# binarybox-barrel.net
KiCad netlist of a schematic drawn in EAGLE
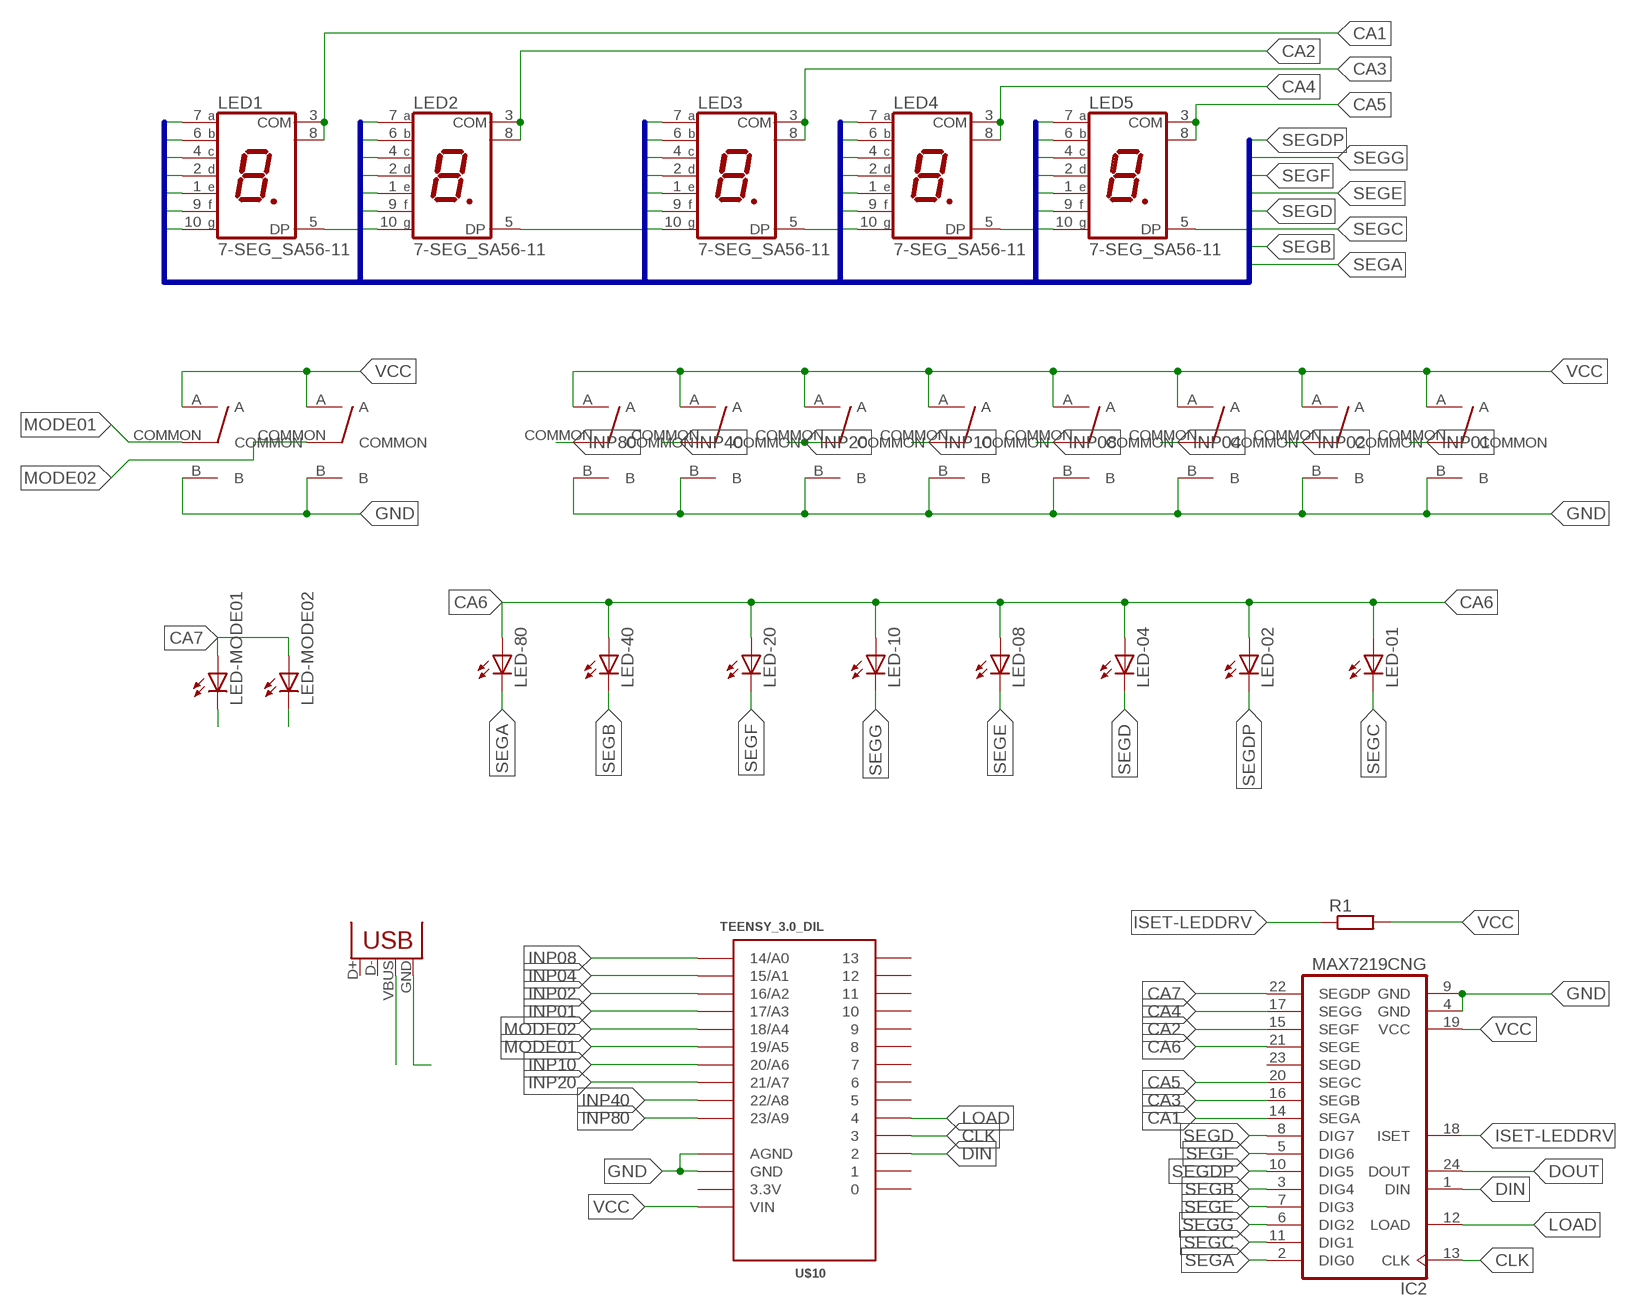
[diagram p0: schematic, sheet 1]

(export (version "E")
  (design (tool "Eeschema 10.0.6"))
  (components
    (comp (ref "IC2")
      (value "MAX7219CNG")
      (footprint "eagle-import:DIL24-3")
      (fields (field (name "MF") "MAXIM"))
      (libsource (lib "eagle-import") (part "MAX7219CNG"))
    )
    (comp (ref "LED-01")
      (value "LED5MM")
      (footprint "eagle-import:LED5MM")
      (libsource (lib "eagle-import") (part "LED5MM"))
    )
    (comp (ref "LED-02")
      (value "LED5MM")
      (footprint "eagle-import:LED5MM")
      (libsource (lib "eagle-import") (part "LED5MM"))
    )
    (comp (ref "LED-04")
      (value "LED5MM")
      (footprint "eagle-import:LED5MM")
      (libsource (lib "eagle-import") (part "LED5MM"))
    )
    (comp (ref "LED-08")
      (value "LED5MM")
      (footprint "eagle-import:LED5MM")
      (libsource (lib "eagle-import") (part "LED5MM"))
    )
    (comp (ref "LED-10")
      (value "LED5MM")
      (footprint "eagle-import:LED5MM")
      (libsource (lib "eagle-import") (part "LED5MM"))
    )
    (comp (ref "LED-20")
      (value "LED5MM")
      (footprint "eagle-import:LED5MM")
      (libsource (lib "eagle-import") (part "LED5MM"))
    )
    (comp (ref "LED-40")
      (value "LED5MM")
      (footprint "eagle-import:LED5MM")
      (libsource (lib "eagle-import") (part "LED5MM"))
    )
    (comp (ref "LED-80")
      (value "LED5MM")
      (footprint "eagle-import:LED5MM")
      (libsource (lib "eagle-import") (part "LED5MM"))
    )
    (comp (ref "LED-MODE01")
      (value "LED5MM")
      (footprint "eagle-import:LED5MM")
      (libsource (lib "eagle-import") (part "LED5MM"))
    )
    (comp (ref "LED-MODE02")
      (value "LED5MM")
      (footprint "eagle-import:LED5MM")
      (libsource (lib "eagle-import") (part "LED5MM"))
    )
    (comp (ref "LED1")
      (value "7-SEG_SA56-11")
      (footprint "eagle-import:SA56-11")
      (libsource (lib "eagle-import") (part "7-SEG_SA56-11"))
    )
    (comp (ref "LED2")
      (value "7-SEG_SA56-11")
      (footprint "eagle-import:SA56-11")
      (libsource (lib "eagle-import") (part "7-SEG_SA56-11"))
    )
    (comp (ref "LED3")
      (value "7-SEG_SA56-11")
      (footprint "eagle-import:SA56-11")
      (libsource (lib "eagle-import") (part "7-SEG_SA56-11"))
    )
    (comp (ref "LED4")
      (value "7-SEG_SA56-11")
      (footprint "eagle-import:SA56-11")
      (libsource (lib "eagle-import") (part "7-SEG_SA56-11"))
    )
    (comp (ref "LED5")
      (value "7-SEG_SA56-11")
      (footprint "eagle-import:SA56-11")
      (libsource (lib "eagle-import") (part "7-SEG_SA56-11"))
    )
    (comp (ref "R1")
      (value "R-EU_0207/10")
      (footprint "eagle-import:0207_10")
      (libsource (lib "eagle-import") (part "R-EU_0207/10"))
    )
    (comp (ref "U$1")
      (value "ARROW-AB-SWITCH")
      (footprint "eagle-import:333-333")
      (libsource (lib "eagle-import") (part "ARROW-AB-SWITCH"))
    )
    (comp (ref "U$2")
      (value "ARROW-AB-SWITCH")
      (footprint "eagle-import:333-333")
      (libsource (lib "eagle-import") (part "ARROW-AB-SWITCH"))
    )
    (comp (ref "U$3")
      (value "ARROW-AB-SWITCH")
      (footprint "eagle-import:333-333")
      (libsource (lib "eagle-import") (part "ARROW-AB-SWITCH"))
    )
    (comp (ref "U$4")
      (value "ARROW-AB-SWITCH")
      (footprint "eagle-import:333-333")
      (libsource (lib "eagle-import") (part "ARROW-AB-SWITCH"))
    )
    (comp (ref "U$5")
      (value "ARROW-AB-SWITCH")
      (footprint "eagle-import:333-333")
      (libsource (lib "eagle-import") (part "ARROW-AB-SWITCH"))
    )
    (comp (ref "U$6")
      (value "ARROW-AB-SWITCH")
      (footprint "eagle-import:333-333")
      (libsource (lib "eagle-import") (part "ARROW-AB-SWITCH"))
    )
    (comp (ref "U$7")
      (value "ARROW-AB-SWITCH")
      (footprint "eagle-import:333-333")
      (libsource (lib "eagle-import") (part "ARROW-AB-SWITCH"))
    )
    (comp (ref "U$8")
      (value "ARROW-AB-SWITCH")
      (footprint "eagle-import:333-333")
      (libsource (lib "eagle-import") (part "ARROW-AB-SWITCH"))
    )
    (comp (ref "U$10")
      (value "TEENSY_3.0_DIL")
      (footprint "eagle-import:TEENSY3-DIL")
      (libsource (lib "eagle-import") (part "TEENSY_3.0_DIL"))
    )
    (comp (ref "U$11")
      (value "ARROW-AB-SWITCH")
      (footprint "eagle-import:333-333")
      (libsource (lib "eagle-import") (part "ARROW-AB-SWITCH"))
    )
    (comp (ref "U$13")
      (value "ARROW-AB-SWITCH")
      (footprint "eagle-import:333-333")
      (libsource (lib "eagle-import") (part "ARROW-AB-SWITCH"))
    )
    (comp (ref "X1")
      (value "USBPTH")
      (footprint "eagle-import:USB-B-PTH")
      (libsource (lib "eagle-import") (part "USBPTH"))
    )
  )
  (nets
    (net (code "1") (name "/3.3V") (class "Default")
      (node (ref "U$10") (pin "3.3V") (pinfunction "3.3V_3.3V") (pintype "power_in"))
    )
    (net (code "2") (name "CA1") (class "Default")
      (node (ref "IC2") (pin "14") (pinfunction "SEGA_14") (pintype "output"))
      (node (ref "LED1") (pin "3") (pinfunction "COM_3") (pintype "passive"))
      (node (ref "LED1") (pin "8") (pinfunction "COM_8") (pintype "passive"))
    )
    (net (code "3") (name "CA2") (class "Default")
      (node (ref "IC2") (pin "15") (pinfunction "SEGF_15") (pintype "output"))
      (node (ref "LED2") (pin "3") (pinfunction "COM_3") (pintype "passive"))
      (node (ref "LED2") (pin "8") (pinfunction "COM_8") (pintype "passive"))
    )
    (net (code "4") (name "CA3") (class "Default")
      (node (ref "IC2") (pin "16") (pinfunction "SEGB_16") (pintype "output"))
      (node (ref "LED3") (pin "3") (pinfunction "COM_3") (pintype "passive"))
      (node (ref "LED3") (pin "8") (pinfunction "COM_8") (pintype "passive"))
    )
    (net (code "5") (name "CA4") (class "Default")
      (node (ref "IC2") (pin "17") (pinfunction "SEGG_17") (pintype "output"))
      (node (ref "LED4") (pin "3") (pinfunction "COM_3") (pintype "passive"))
      (node (ref "LED4") (pin "8") (pinfunction "COM_8") (pintype "passive"))
    )
    (net (code "6") (name "CA5") (class "Default")
      (node (ref "IC2") (pin "20") (pinfunction "SEGC_20") (pintype "output"))
      (node (ref "LED5") (pin "3") (pinfunction "COM_3") (pintype "passive"))
      (node (ref "LED5") (pin "8") (pinfunction "COM_8") (pintype "passive"))
    )
    (net (code "7") (name "CA6") (class "Default")
      (node (ref "IC2") (pin "21") (pinfunction "SEGE_21") (pintype "output"))
      (node (ref "LED-01") (pin "A") (pinfunction "A_A") (pintype "passive"))
      (node (ref "LED-02") (pin "A") (pinfunction "A_A") (pintype "passive"))
      (node (ref "LED-04") (pin "A") (pinfunction "A_A") (pintype "passive"))
      (node (ref "LED-08") (pin "A") (pinfunction "A_A") (pintype "passive"))
      (node (ref "LED-10") (pin "A") (pinfunction "A_A") (pintype "passive"))
      (node (ref "LED-20") (pin "A") (pinfunction "A_A") (pintype "passive"))
      (node (ref "LED-40") (pin "A") (pinfunction "A_A") (pintype "passive"))
      (node (ref "LED-80") (pin "A") (pinfunction "A_A") (pintype "passive"))
    )
    (net (code "8") (name "CA7") (class "Default")
      (node (ref "IC2") (pin "22") (pinfunction "SEGDP_22") (pintype "output"))
      (node (ref "LED-MODE01") (pin "A") (pinfunction "A_A") (pintype "passive"))
      (node (ref "LED-MODE02") (pin "A") (pinfunction "A_A") (pintype "passive"))
    )
    (net (code "9") (name "CLK") (class "Default")
      (node (ref "IC2") (pin "13") (pinfunction "CLK_13") (pintype "input"))
      (node (ref "U$10") (pin "3") (pinfunction "3_3") (pintype "bidirectional"))
    )
    (net (code "10") (name "DIN") (class "Default")
      (node (ref "IC2") (pin "1") (pinfunction "DIN_1") (pintype "input"))
      (node (ref "U$10") (pin "2") (pinfunction "2_2") (pintype "bidirectional"))
    )
    (net (code "11") (name "DOUT") (class "Default")
      (node (ref "IC2") (pin "24") (pinfunction "DOUT_24") (pintype "output"))
    )
    (net (code "12") (name "GND") (class "Default")
      (node (ref "IC2") (pin "4") (pinfunction "GND_4") (pintype "power_in"))
      (node (ref "IC2") (pin "9") (pinfunction "GND_9") (pintype "power_in"))
      (node (ref "U$1") (pin "B") (pinfunction "B_B") (pintype "bidirectional"))
      (node (ref "U$10") (pin "AGND") (pinfunction "AGND_AGND") (pintype "power_in"))
      (node (ref "U$10") (pin "GND") (pinfunction "GND_GND") (pintype "power_in"))
      (node (ref "U$11") (pin "B") (pinfunction "B_B") (pintype "bidirectional"))
      (node (ref "U$13") (pin "B") (pinfunction "B_B") (pintype "bidirectional"))
      (node (ref "U$2") (pin "B") (pinfunction "B_B") (pintype "bidirectional"))
      (node (ref "U$3") (pin "B") (pinfunction "B_B") (pintype "bidirectional"))
      (node (ref "U$4") (pin "B") (pinfunction "B_B") (pintype "bidirectional"))
      (node (ref "U$5") (pin "B") (pinfunction "B_B") (pintype "bidirectional"))
      (node (ref "U$6") (pin "B") (pinfunction "B_B") (pintype "bidirectional"))
      (node (ref "U$7") (pin "B") (pinfunction "B_B") (pintype "bidirectional"))
      (node (ref "U$8") (pin "B") (pinfunction "B_B") (pintype "bidirectional"))
      (node (ref "X1") (pin "GND") (pinfunction "GND_GND") (pintype "bidirectional"))
    )
    (net (code "13") (name "INP01") (class "Default")
      (node (ref "U$10") (pin "17/A3") (pinfunction "17/A3_17/A3") (pintype "bidirectional"))
      (node (ref "U$8") (pin "COMMON") (pinfunction "COMMON_COMMON") (pintype "bidirectional"))
    )
    (net (code "14") (name "INP02") (class "Default")
      (node (ref "U$10") (pin "16/A2") (pinfunction "16/A2_16/A2") (pintype "bidirectional"))
      (node (ref "U$7") (pin "COMMON") (pinfunction "COMMON_COMMON") (pintype "bidirectional"))
    )
    (net (code "15") (name "INP04") (class "Default")
      (node (ref "U$10") (pin "15/A1") (pinfunction "15/A1_15/A1") (pintype "bidirectional"))
      (node (ref "U$6") (pin "COMMON") (pinfunction "COMMON_COMMON") (pintype "bidirectional"))
    )
    (net (code "16") (name "INP08") (class "Default")
      (node (ref "U$10") (pin "14/A0") (pinfunction "14/A0_14/A0") (pintype "bidirectional"))
      (node (ref "U$5") (pin "COMMON") (pinfunction "COMMON_COMMON") (pintype "bidirectional"))
    )
    (net (code "17") (name "INP10") (class "Default")
      (node (ref "U$10") (pin "20/A6") (pinfunction "20/A6_20/A6") (pintype "bidirectional"))
      (node (ref "U$4") (pin "COMMON") (pinfunction "COMMON_COMMON") (pintype "bidirectional"))
    )
    (net (code "18") (name "INP20") (class "Default")
      (node (ref "U$10") (pin "21/A7") (pinfunction "21/A7_21/A7") (pintype "bidirectional"))
      (node (ref "U$3") (pin "COMMON") (pinfunction "COMMON_COMMON") (pintype "bidirectional"))
    )
    (net (code "19") (name "INP40") (class "Default")
      (node (ref "U$10") (pin "22/A8") (pinfunction "22/A8_22/A8") (pintype "bidirectional"))
      (node (ref "U$2") (pin "COMMON") (pinfunction "COMMON_COMMON") (pintype "bidirectional"))
    )
    (net (code "20") (name "INP80") (class "Default")
      (node (ref "U$1") (pin "COMMON") (pinfunction "COMMON_COMMON") (pintype "bidirectional"))
      (node (ref "U$10") (pin "23/A9") (pinfunction "23/A9_23/A9") (pintype "bidirectional"))
    )
    (net (code "21") (name "ISET-LEDDRV") (class "Default")
      (node (ref "IC2") (pin "18") (pinfunction "ISET_18") (pintype "input"))
      (node (ref "R1") (pin "1") (pinfunction "1_1") (pintype "passive"))
    )
    (net (code "22") (name "LOAD") (class "Default")
      (node (ref "IC2") (pin "12") (pinfunction "LOAD_12") (pintype "input"))
      (node (ref "U$10") (pin "4") (pinfunction "4_4") (pintype "bidirectional"))
    )
    (net (code "23") (name "MODE01") (class "Default")
      (node (ref "U$10") (pin "19/A5") (pinfunction "19/A5_19/A5") (pintype "bidirectional"))
      (node (ref "U$11") (pin "COMMON") (pinfunction "COMMON_COMMON") (pintype "bidirectional"))
    )
    (net (code "24") (name "MODE02") (class "Default")
      (node (ref "U$10") (pin "18/A4") (pinfunction "18/A4_18/A4") (pintype "bidirectional"))
      (node (ref "U$13") (pin "COMMON") (pinfunction "COMMON_COMMON") (pintype "bidirectional"))
    )
    (net (code "25") (name "SEGA") (class "Default")
      (node (ref "IC2") (pin "2") (pinfunction "DIG0_2") (pintype "output"))
      (node (ref "LED-80") (pin "K") (pinfunction "C_K") (pintype "passive"))
      (node (ref "LED1") (pin "7") (pinfunction "A_7") (pintype "passive"))
      (node (ref "LED2") (pin "7") (pinfunction "A_7") (pintype "passive"))
      (node (ref "LED3") (pin "7") (pinfunction "A_7") (pintype "passive"))
      (node (ref "LED4") (pin "7") (pinfunction "A_7") (pintype "passive"))
      (node (ref "LED5") (pin "7") (pinfunction "A_7") (pintype "passive"))
    )
    (net (code "26") (name "SEGB") (class "Default")
      (node (ref "IC2") (pin "3") (pinfunction "DIG4_3") (pintype "output"))
      (node (ref "LED-40") (pin "K") (pinfunction "C_K") (pintype "passive"))
      (node (ref "LED1") (pin "6") (pinfunction "B_6") (pintype "passive"))
      (node (ref "LED2") (pin "6") (pinfunction "B_6") (pintype "passive"))
      (node (ref "LED3") (pin "6") (pinfunction "B_6") (pintype "passive"))
      (node (ref "LED4") (pin "6") (pinfunction "B_6") (pintype "passive"))
      (node (ref "LED5") (pin "6") (pinfunction "B_6") (pintype "passive"))
    )
    (net (code "27") (name "SEGC") (class "Default")
      (node (ref "IC2") (pin "11") (pinfunction "DIG1_11") (pintype "output"))
      (node (ref "LED-01") (pin "K") (pinfunction "C_K") (pintype "passive"))
      (node (ref "LED-MODE01") (pin "K") (pinfunction "C_K") (pintype "passive"))
      (node (ref "LED1") (pin "4") (pinfunction "C_4") (pintype "passive"))
      (node (ref "LED2") (pin "4") (pinfunction "C_4") (pintype "passive"))
      (node (ref "LED3") (pin "4") (pinfunction "C_4") (pintype "passive"))
      (node (ref "LED4") (pin "4") (pinfunction "C_4") (pintype "passive"))
      (node (ref "LED5") (pin "4") (pinfunction "C_4") (pintype "passive"))
    )
    (net (code "28") (name "SEGD") (class "Default")
      (node (ref "IC2") (pin "8") (pinfunction "DIG7_8") (pintype "output"))
      (node (ref "LED-04") (pin "K") (pinfunction "C_K") (pintype "passive"))
      (node (ref "LED1") (pin "2") (pinfunction "D_2") (pintype "passive"))
      (node (ref "LED2") (pin "2") (pinfunction "D_2") (pintype "passive"))
      (node (ref "LED3") (pin "2") (pinfunction "D_2") (pintype "passive"))
      (node (ref "LED4") (pin "2") (pinfunction "D_2") (pintype "passive"))
      (node (ref "LED5") (pin "2") (pinfunction "D_2") (pintype "passive"))
    )
    (net (code "29") (name "SEGDP") (class "Default")
      (node (ref "IC2") (pin "10") (pinfunction "DIG5_10") (pintype "output"))
      (node (ref "LED-02") (pin "K") (pinfunction "C_K") (pintype "passive"))
      (node (ref "LED-MODE02") (pin "K") (pinfunction "C_K") (pintype "passive"))
      (node (ref "LED1") (pin "5") (pinfunction "DP_5") (pintype "passive"))
      (node (ref "LED2") (pin "5") (pinfunction "DP_5") (pintype "passive"))
      (node (ref "LED3") (pin "5") (pinfunction "DP_5") (pintype "passive"))
      (node (ref "LED4") (pin "5") (pinfunction "DP_5") (pintype "passive"))
      (node (ref "LED5") (pin "5") (pinfunction "DP_5") (pintype "passive"))
    )
    (net (code "30") (name "SEGE") (class "Default")
      (node (ref "IC2") (pin "7") (pinfunction "DIG3_7") (pintype "output"))
      (node (ref "LED-08") (pin "K") (pinfunction "C_K") (pintype "passive"))
      (node (ref "LED1") (pin "1") (pinfunction "E_1") (pintype "passive"))
      (node (ref "LED2") (pin "1") (pinfunction "E_1") (pintype "passive"))
      (node (ref "LED3") (pin "1") (pinfunction "E_1") (pintype "passive"))
      (node (ref "LED4") (pin "1") (pinfunction "E_1") (pintype "passive"))
      (node (ref "LED5") (pin "1") (pinfunction "E_1") (pintype "passive"))
    )
    (net (code "31") (name "SEGF") (class "Default")
      (node (ref "IC2") (pin "5") (pinfunction "DIG6_5") (pintype "output"))
      (node (ref "LED-20") (pin "K") (pinfunction "C_K") (pintype "passive"))
      (node (ref "LED1") (pin "9") (pinfunction "F_9") (pintype "passive"))
      (node (ref "LED2") (pin "9") (pinfunction "F_9") (pintype "passive"))
      (node (ref "LED3") (pin "9") (pinfunction "F_9") (pintype "passive"))
      (node (ref "LED4") (pin "9") (pinfunction "F_9") (pintype "passive"))
      (node (ref "LED5") (pin "9") (pinfunction "F_9") (pintype "passive"))
    )
    (net (code "32") (name "SEGG") (class "Default")
      (node (ref "IC2") (pin "6") (pinfunction "DIG2_6") (pintype "output"))
      (node (ref "LED-10") (pin "K") (pinfunction "C_K") (pintype "passive"))
      (node (ref "LED1") (pin "10") (pinfunction "G_10") (pintype "passive"))
      (node (ref "LED2") (pin "10") (pinfunction "G_10") (pintype "passive"))
      (node (ref "LED3") (pin "10") (pinfunction "G_10") (pintype "passive"))
      (node (ref "LED4") (pin "10") (pinfunction "G_10") (pintype "passive"))
      (node (ref "LED5") (pin "10") (pinfunction "G_10") (pintype "passive"))
    )
    (net (code "33") (name "VCC") (class "Default")
      (node (ref "IC2") (pin "19") (pinfunction "VCC_19") (pintype "power_in"))
      (node (ref "R1") (pin "2") (pinfunction "2_2") (pintype "passive"))
      (node (ref "U$1") (pin "A") (pinfunction "A_A") (pintype "bidirectional"))
      (node (ref "U$10") (pin "VIN") (pinfunction "VIN_VIN") (pintype "power_in"))
      (node (ref "U$11") (pin "A") (pinfunction "A_A") (pintype "bidirectional"))
      (node (ref "U$13") (pin "A") (pinfunction "A_A") (pintype "bidirectional"))
      (node (ref "U$2") (pin "A") (pinfunction "A_A") (pintype "bidirectional"))
      (node (ref "U$3") (pin "A") (pinfunction "A_A") (pintype "bidirectional"))
      (node (ref "U$4") (pin "A") (pinfunction "A_A") (pintype "bidirectional"))
      (node (ref "U$5") (pin "A") (pinfunction "A_A") (pintype "bidirectional"))
      (node (ref "U$6") (pin "A") (pinfunction "A_A") (pintype "bidirectional"))
      (node (ref "U$7") (pin "A") (pinfunction "A_A") (pintype "bidirectional"))
      (node (ref "U$8") (pin "A") (pinfunction "A_A") (pintype "bidirectional"))
      (node (ref "X1") (pin "VBUS") (pinfunction "VBUS_VBUS") (pintype "bidirectional"))
    )
    (net (code "34") (name "unconnected-(IC2-SEGD-Pad23)") (class "Default")
      (node (ref "IC2") (pin "23") (pinfunction "SEGD_23") (pintype "output"))
    )
    (net (code "35") (name "unconnected-(U$10-Pad0)") (class "Default")
      (node (ref "U$10") (pin "0") (pinfunction "0_0") (pintype "bidirectional"))
    )
    (net (code "36") (name "unconnected-(U$10-Pad1)") (class "Default")
      (node (ref "U$10") (pin "1") (pinfunction "1_1") (pintype "bidirectional"))
    )
    (net (code "37") (name "unconnected-(U$10-Pad5)") (class "Default")
      (node (ref "U$10") (pin "5") (pinfunction "5_5") (pintype "bidirectional"))
    )
    (net (code "38") (name "unconnected-(U$10-Pad6)") (class "Default")
      (node (ref "U$10") (pin "6") (pinfunction "6_6") (pintype "bidirectional"))
    )
    (net (code "39") (name "unconnected-(U$10-Pad7)") (class "Default")
      (node (ref "U$10") (pin "7") (pinfunction "7_7") (pintype "bidirectional"))
    )
    (net (code "40") (name "unconnected-(U$10-Pad8)") (class "Default")
      (node (ref "U$10") (pin "8") (pinfunction "8_8") (pintype "bidirectional"))
    )
    (net (code "41") (name "unconnected-(U$10-Pad9)") (class "Default")
      (node (ref "U$10") (pin "9") (pinfunction "9_9") (pintype "bidirectional"))
    )
    (net (code "42") (name "unconnected-(U$10-Pad10)") (class "Default")
      (node (ref "U$10") (pin "10") (pinfunction "10_10") (pintype "bidirectional"))
    )
    (net (code "43") (name "unconnected-(U$10-Pad11)") (class "Default")
      (node (ref "U$10") (pin "11") (pinfunction "11_11") (pintype "bidirectional"))
    )
    (net (code "44") (name "unconnected-(U$10-Pad12)") (class "Default")
      (node (ref "U$10") (pin "12") (pinfunction "12_12") (pintype "bidirectional"))
    )
    (net (code "45") (name "unconnected-(U$10-Pad13)") (class "Default")
      (node (ref "U$10") (pin "13") (pinfunction "13_13") (pintype "bidirectional"))
    )
    (net (code "46") (name "unconnected-(X1-PadD+)") (class "Default")
      (node (ref "X1") (pin "D+") (pinfunction "D+_D+") (pintype "bidirectional"))
    )
    (net (code "47") (name "unconnected-(X1-PadD-)") (class "Default")
      (node (ref "X1") (pin "D-") (pinfunction "D-_D-") (pintype "bidirectional"))
    )
  )
)
